# 4__RFM95W.net
KiCad netlist of a schematic drawn in Altium Designer
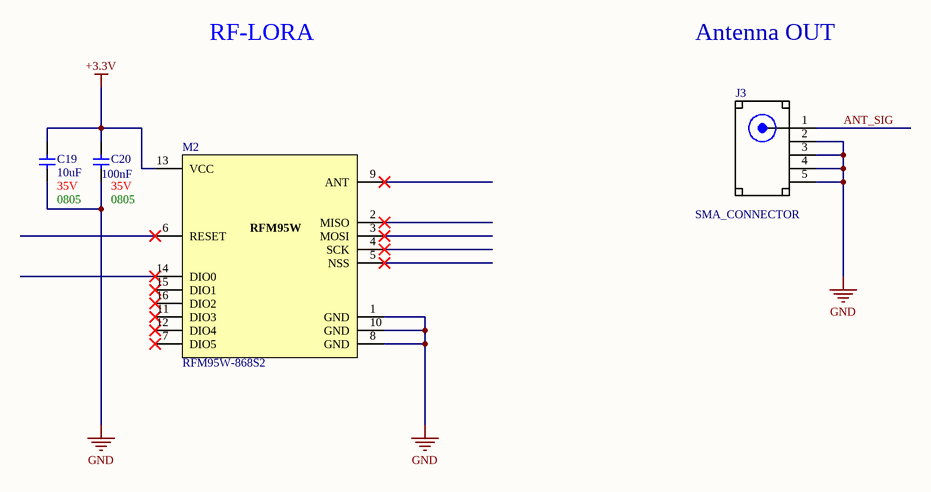
[diagram p0: [4]_RFM95W.SchDoc]

(export (version "E")
  (design (tool "Eeschema 10.0.6"))
  (components
    (comp (ref "C19")
      (value "10uF")
      (footprint "Capacitor_0805")
      (description "Ceramic Capacitor SMD 0805")
      (fields
        (field (name "TOLERANCE") "10%")
        (field (name "VOLTAGE") "35V")
        (field (name "PACKAGE") "0805")
        (field (name "Comment") "Capacitor SMD 0805")
      )
      (libsource (lib "AKN_PI_Library") (part "Capacitor SMD 0805"))
    )
    (comp (ref "C20")
      (value "100nF")
      (footprint "Capacitor_0805")
      (description "Ceramic Capacitor SMD 0805")
      (fields
        (field (name "TOLERANCE") "10%")
        (field (name "VOLTAGE") "35V")
        (field (name "PACKAGE") "0805")
        (field (name "Comment") "Capacitor SMD 0805")
      )
      (libsource (lib "AKN_PI_Library") (part "Capacitor SMD 0805"))
    )
    (comp (ref "J3")
      (value "SMA_CONNECTOR")
      (footprint "LPRS_SMA_CONNECTOR")
      (fields (field (name "MP") "SMA CONNECTOR") (field (name "MF") "LPRS"))
      (libsource (lib "SMA_CONNECTOR") (part "SMA_CONNECTOR"))
    )
    (comp (ref "M2")
      (value "RFM95W-868S2")
      (footprint "RFM95W-868S2")
      (description "HOPE MICROELECTRONICS RFM95W-868S2 - LoRa RF Module")
      (libsource (lib "AKN_PI_Library") (part "RFM95W"))
    )
  )
  (nets
    (net (code "1") (name "+3.3V") (class "Default")
      (node (ref "C19") (pin "2") (pinfunction "2_2") (pintype "passive"))
      (node (ref "C20") (pin "2") (pinfunction "2_2") (pintype "passive"))
      (node (ref "M2") (pin "13") (pinfunction "VCC_13") (pintype "passive"))
    )
    (net (code "2") (name "/ANT_SIG") (class "Default")
      (node (ref "J3") (pin "1") (pinfunction "ANT_1") (pintype "passive"))
    )
    (net (code "5") (name "GND") (class "Default")
      (node (ref "C19") (pin "1") (pinfunction "1_1") (pintype "passive"))
      (node (ref "C20") (pin "1") (pinfunction "1_1") (pintype "passive"))
      (node (ref "J3") (pin "2") (pinfunction "GND_2") (pintype "passive"))
      (node (ref "J3") (pin "3") (pinfunction "GND_3") (pintype "passive"))
      (node (ref "J3") (pin "4") (pinfunction "GND_4") (pintype "passive"))
      (node (ref "J3") (pin "5") (pinfunction "GND_5") (pintype "passive"))
      (node (ref "M2") (pin "1") (pinfunction "GND_1") (pintype "passive"))
      (node (ref "M2") (pin "10") (pinfunction "GND_10") (pintype "passive"))
      (node (ref "M2") (pin "8") (pinfunction "GND_8") (pintype "passive"))
    )
    (net (code "6") (name "unconnected-(M2-ANT-Pad9)") (class "Default")
      (node (ref "M2") (pin "9") (pinfunction "ANT_9") (pintype "passive+no_connect"))
    )
    (net (code "7") (name "unconnected-(M2-DIO0-Pad14)") (class "Default")
      (node (ref "M2") (pin "14") (pinfunction "DIO0_14") (pintype "passive+no_connect"))
    )
    (net (code "8") (name "unconnected-(M2-DIO1-Pad15)") (class "Default")
      (node (ref "M2") (pin "15") (pinfunction "DIO1_15") (pintype "passive+no_connect"))
    )
    (net (code "9") (name "unconnected-(M2-DIO2-Pad16)") (class "Default")
      (node (ref "M2") (pin "16") (pinfunction "DIO2_16") (pintype "passive+no_connect"))
    )
    (net (code "10") (name "unconnected-(M2-DIO3-Pad11)") (class "Default")
      (node (ref "M2") (pin "11") (pinfunction "DIO3_11") (pintype "passive+no_connect"))
    )
    (net (code "11") (name "unconnected-(M2-DIO4-Pad12)") (class "Default")
      (node (ref "M2") (pin "12") (pinfunction "DIO4_12") (pintype "passive+no_connect"))
    )
    (net (code "12") (name "unconnected-(M2-DIO5-Pad7)") (class "Default")
      (node (ref "M2") (pin "7") (pinfunction "DIO5_7") (pintype "passive+no_connect"))
    )
    (net (code "13") (name "unconnected-(M2-MISO-Pad2)") (class "Default")
      (node (ref "M2") (pin "2") (pinfunction "MISO_2") (pintype "passive+no_connect"))
    )
    (net (code "14") (name "unconnected-(M2-MOSI-Pad3)") (class "Default")
      (node (ref "M2") (pin "3") (pinfunction "MOSI_3") (pintype "passive+no_connect"))
    )
    (net (code "15") (name "unconnected-(M2-NSS-Pad5)") (class "Default")
      (node (ref "M2") (pin "5") (pinfunction "NSS_5") (pintype "passive+no_connect"))
    )
    (net (code "16") (name "unconnected-(M2-RESET-Pad6)") (class "Default")
      (node (ref "M2") (pin "6") (pinfunction "RESET_6") (pintype "passive+no_connect"))
    )
    (net (code "17") (name "unconnected-(M2-SCK-Pad4)") (class "Default")
      (node (ref "M2") (pin "4") (pinfunction "SCK_4") (pintype "passive+no_connect"))
    )
  )
)
